# T15_PRI_SYS_V1_0.net
KiCad netlist of a schematic drawn in EAGLE
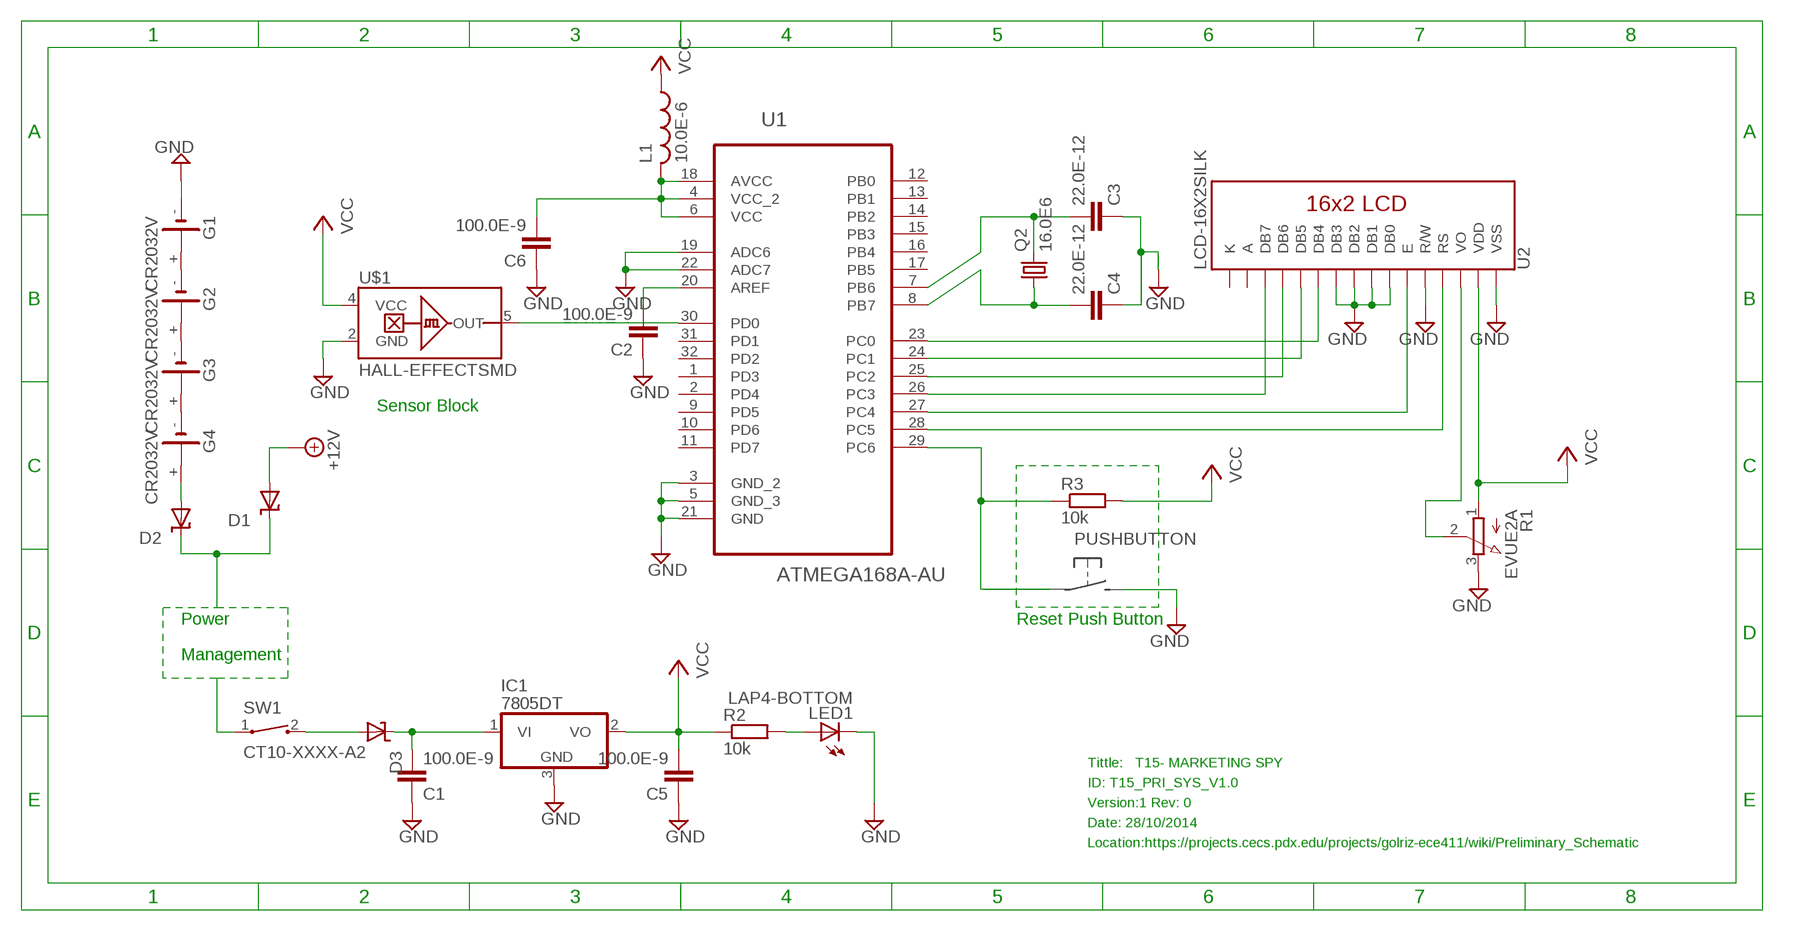
[diagram p0: schematic, sheet 1]

(export (version "E")
  (design (tool "Eeschema 10.0.6"))
  (components
    (comp (ref "C1")
      (value "100.0E-9")
      (footprint "eagle-import:C025-024X044")
      (libsource (lib "eagle-import") (part "C-EU025-024X044"))
    )
    (comp (ref "C2")
      (value "100.0E-9")
      (footprint "eagle-import:C025-024X044")
      (libsource (lib "eagle-import") (part "C-EU025-024X044"))
    )
    (comp (ref "C3")
      (value "22.0E-12")
      (footprint "eagle-import:C025-024X044")
      (libsource (lib "eagle-import") (part "C-EU025-024X044"))
    )
    (comp (ref "C4")
      (value "22.0E-12")
      (footprint "eagle-import:C025-024X044")
      (libsource (lib "eagle-import") (part "C-EU025-024X044"))
    )
    (comp (ref "C5")
      (value "100.0E-9")
      (footprint "eagle-import:C025-024X044")
      (libsource (lib "eagle-import") (part "C-EU025-024X044"))
    )
    (comp (ref "C6")
      (value "100.0E-9")
      (footprint "eagle-import:C025-024X044")
      (libsource (lib "eagle-import") (part "C-EU025-024X044"))
    )
    (comp (ref "D1")
      (value "SUPPRESSOR-SMBJ")
      (footprint "eagle-import:SMBJ")
      (libsource (lib "eagle-import") (part "SUPPRESSOR-SMBJ"))
    )
    (comp (ref "D2")
      (value "SUPPRESSOR-SMBJ")
      (footprint "eagle-import:SMBJ")
      (libsource (lib "eagle-import") (part "SUPPRESSOR-SMBJ"))
    )
    (comp (ref "D3")
      (value "SUPPRESSOR-SMBJ")
      (footprint "eagle-import:SMBJ")
      (libsource (lib "eagle-import") (part "SUPPRESSOR-SMBJ"))
    )
    (comp (ref "G1")
      (value "CR2032V")
      (footprint "eagle-import:CR2032V")
      (libsource (lib "eagle-import") (part "CR2032V"))
    )
    (comp (ref "G2")
      (value "CR2032V")
      (footprint "eagle-import:CR2032V")
      (libsource (lib "eagle-import") (part "CR2032V"))
    )
    (comp (ref "G3")
      (value "CR2032V")
      (footprint "eagle-import:CR2032V")
      (libsource (lib "eagle-import") (part "CR2032V"))
    )
    (comp (ref "G4")
      (value "CR2032V")
      (footprint "eagle-import:CR2032V")
      (libsource (lib "eagle-import") (part "CR2032V"))
    )
    (comp (ref "IC1")
      (value "7805DT")
      (footprint "eagle-import:TO252")
      (libsource (lib "eagle-import") (part "78DT05"))
    )
    (comp (ref "L1")
      (value "10.0E-6")
      (footprint "eagle-import:0204_5")
      (libsource (lib "eagle-import") (part "L-US0204/5"))
    )
    (comp (ref "LED1")
      (value "LAP4-BOTTOM")
      (footprint "eagle-import:P47F-BOTTOM")
      (libsource (lib "eagle-import") (part "P4-BOTTOMLA"))
    )
    (comp (ref "Q2")
      (value "16.0E6")
      (footprint "eagle-import:HC49_S")
      (libsource (lib "eagle-import") (part "CRYSTALHC49S"))
    )
    (comp (ref "R1")
      (value "EVUE2A")
      (footprint "eagle-import:EVUE")
      (libsource (lib "eagle-import") (part "EVUE2A"))
    )
    (comp (ref "R2")
      (value "10k")
      (footprint "eagle-import:0204_5")
      (libsource (lib "eagle-import") (part "R-EU_0204/5"))
    )
    (comp (ref "R3")
      (value "10k")
      (footprint "eagle-import:0204_5")
      (libsource (lib "eagle-import") (part "R-EU_0204/5"))
    )
    (comp (ref "SW1")
      (value "CT10-XXXX-A2")
      (footprint "eagle-import:CT10-XXXX-A2")
      (libsource (lib "eagle-import") (part "CT10-XXXX-A2"))
    )
    (comp (ref "U$1")
      (value "HALL-EFFECTSMD")
      (footprint "eagle-import:SC70")
      (libsource (lib "eagle-import") (part "HALL-EFFECTSMD"))
    )
    (comp (ref "U1")
      (value "ATMEGA168A-AU")
      (footprint "eagle-import:QFP80P900X900X120-32N")
      (libsource (lib "eagle-import") (part "ATMEGA168A-AU"))
    )
    (comp (ref "U2")
      (value "LCD-16X2SILK")
      (footprint "eagle-import:LCD-16X2")
      (libsource (lib "eagle-import") (part "LCD-16X2SILK"))
    )
  )
  (nets
    (net (code "1") (name "+12V") (class "Default")
      (node (ref "D1") (pin "A") (pinfunction "A_A") (pintype "passive"))
    )
    (net (code "2") (name "/A") (class "Default")
      (node (ref "U2") (pin "15") (pinfunction "A_15") (pintype "power_in"))
    )
    (net (code "3") (name "/K") (class "Default")
      (node (ref "U2") (pin "16") (pinfunction "K_16") (pintype "power_in"))
    )
    (net (code "4") (name "GND") (class "Default")
      (node (ref "C1") (pin "1") (pinfunction "1_1") (pintype "passive"))
      (node (ref "C2") (pin "1") (pinfunction "1_1") (pintype "passive"))
      (node (ref "C3") (pin "1") (pinfunction "1_1") (pintype "passive"))
      (node (ref "C4") (pin "1") (pinfunction "1_1") (pintype "passive"))
      (node (ref "C5") (pin "1") (pinfunction "1_1") (pintype "passive"))
      (node (ref "C6") (pin "1") (pinfunction "1_1") (pintype "passive"))
      (node (ref "G1") (pin "-") (pinfunction "-_-") (pintype "passive"))
      (node (ref "IC1") (pin "3") (pinfunction "GND_3") (pintype "passive"))
      (node (ref "LED1") (pin "C") (pinfunction "C_C") (pintype "passive"))
      (node (ref "R1") (pin "3") (pinfunction "E_3") (pintype "passive"))
      (node (ref "U$1") (pin "2") (pinfunction "GND_2") (pintype "bidirectional"))
      (node (ref "U1") (pin "19") (pinfunction "ADC6_19") (pintype "input"))
      (node (ref "U1") (pin "21") (pinfunction "GND_21") (pintype "passive"))
      (node (ref "U1") (pin "22") (pinfunction "ADC7_22") (pintype "input"))
      (node (ref "U1") (pin "3") (pinfunction "GND_2_3") (pintype "passive"))
      (node (ref "U1") (pin "5") (pinfunction "GND_3_5") (pintype "passive"))
      (node (ref "U2") (pin "1") (pinfunction "VSS_1") (pintype "power_in"))
      (node (ref "U2") (pin "10") (pinfunction "DB3_10") (pintype "bidirectional"))
      (node (ref "U2") (pin "5") (pinfunction "R/W_5") (pintype "input"))
      (node (ref "U2") (pin "7") (pinfunction "DB0_7") (pintype "bidirectional"))
      (node (ref "U2") (pin "8") (pinfunction "DB1_8") (pintype "bidirectional"))
      (node (ref "U2") (pin "9") (pinfunction "DB2_9") (pintype "bidirectional"))
    )
    (net (code "5") (name "Net-(D1-PadC)") (class "Default")
      (node (ref "D1") (pin "C") (pinfunction "C_C") (pintype "passive"))
      (node (ref "D2") (pin "C") (pinfunction "C_C") (pintype "passive"))
      (node (ref "SW1") (pin "1") (pinfunction "1_1") (pintype "passive"))
    )
    (net (code "6") (name "Net-(D2-PadA)") (class "Default")
      (node (ref "D2") (pin "A") (pinfunction "A_A") (pintype "passive"))
      (node (ref "G4") (pin "+") (pinfunction "+_+") (pintype "passive"))
    )
    (net (code "7") (name "Net-(D3-PadA)") (class "Default")
      (node (ref "D3") (pin "A") (pinfunction "A_A") (pintype "passive"))
      (node (ref "SW1") (pin "2") (pinfunction "2_2") (pintype "passive"))
    )
    (net (code "8") (name "Net-(G1-Pad+)") (class "Default")
      (node (ref "G1") (pin "+") (pinfunction "+_+") (pintype "passive"))
      (node (ref "G2") (pin "-") (pinfunction "-_-") (pintype "passive"))
    )
    (net (code "9") (name "Net-(G2-Pad+)") (class "Default")
      (node (ref "G2") (pin "+") (pinfunction "+_+") (pintype "passive"))
      (node (ref "G3") (pin "-") (pinfunction "-_-") (pintype "passive"))
    )
    (net (code "10") (name "Net-(G3-Pad+)") (class "Default")
      (node (ref "G3") (pin "+") (pinfunction "+_+") (pintype "passive"))
      (node (ref "G4") (pin "-") (pinfunction "-_-") (pintype "passive"))
    )
    (net (code "11") (name "Net-(IC1-VI)") (class "Default")
      (node (ref "C1") (pin "2") (pinfunction "2_2") (pintype "passive"))
      (node (ref "D3") (pin "C") (pinfunction "C_C") (pintype "passive"))
      (node (ref "IC1") (pin "1") (pinfunction "VI_1") (pintype "input"))
    )
    (net (code "12") (name "Net-(LED1-PadA)") (class "Default")
      (node (ref "LED1") (pin "A") (pinfunction "A_A") (pintype "passive"))
      (node (ref "R2") (pin "2") (pinfunction "2_2") (pintype "passive"))
    )
    (net (code "13") (name "Net-(R1-S)") (class "Default")
      (node (ref "R1") (pin "2") (pinfunction "S_2") (pintype "passive"))
      (node (ref "U2") (pin "3") (pinfunction "VO_3") (pintype "bidirectional"))
    )
    (net (code "14") (name "Net-(U$1-OUT)") (class "Default")
      (node (ref "U$1") (pin "5") (pinfunction "OUT_5") (pintype "bidirectional"))
      (node (ref "U1") (pin "30") (pinfunction "PD0_30") (pintype "bidirectional"))
    )
    (net (code "15") (name "Net-(U1-AREF)") (class "Default")
      (node (ref "C2") (pin "2") (pinfunction "2_2") (pintype "passive"))
      (node (ref "U1") (pin "20") (pinfunction "AREF_20") (pintype "input"))
    )
    (net (code "16") (name "Net-(U1-AVCC)") (class "Default")
      (node (ref "C6") (pin "2") (pinfunction "2_2") (pintype "passive"))
      (node (ref "L1") (pin "2") (pinfunction "2_2") (pintype "passive"))
      (node (ref "U1") (pin "18") (pinfunction "AVCC_18") (pintype "power_in"))
      (node (ref "U1") (pin "4") (pinfunction "VCC_2_4") (pintype "power_in"))
      (node (ref "U1") (pin "6") (pinfunction "VCC_6") (pintype "power_in"))
    )
    (net (code "17") (name "Net-(U1-PB6)") (class "Default")
      (node (ref "C3") (pin "2") (pinfunction "2_2") (pintype "passive"))
      (node (ref "Q2") (pin "2") (pinfunction "2_2") (pintype "passive"))
      (node (ref "U1") (pin "7") (pinfunction "PB6_7") (pintype "bidirectional"))
    )
    (net (code "18") (name "Net-(U1-PB7)") (class "Default")
      (node (ref "C4") (pin "2") (pinfunction "2_2") (pintype "passive"))
      (node (ref "Q2") (pin "1") (pinfunction "1_1") (pintype "passive"))
      (node (ref "U1") (pin "8") (pinfunction "PB7_8") (pintype "bidirectional"))
    )
    (net (code "19") (name "Net-(U1-PC0)") (class "Default")
      (node (ref "U1") (pin "23") (pinfunction "PC0_23") (pintype "bidirectional"))
      (node (ref "U2") (pin "11") (pinfunction "DB4_11") (pintype "bidirectional"))
    )
    (net (code "20") (name "Net-(U1-PC1)") (class "Default")
      (node (ref "U1") (pin "24") (pinfunction "PC1_24") (pintype "bidirectional"))
      (node (ref "U2") (pin "12") (pinfunction "DB5_12") (pintype "bidirectional"))
    )
    (net (code "21") (name "Net-(U1-PC2)") (class "Default")
      (node (ref "U1") (pin "25") (pinfunction "PC2_25") (pintype "bidirectional"))
      (node (ref "U2") (pin "13") (pinfunction "DB6_13") (pintype "bidirectional"))
    )
    (net (code "22") (name "Net-(U1-PC3)") (class "Default")
      (node (ref "U1") (pin "26") (pinfunction "PC3_26") (pintype "bidirectional"))
      (node (ref "U2") (pin "14") (pinfunction "DB7_14") (pintype "bidirectional"))
    )
    (net (code "23") (name "Net-(U1-PC4)") (class "Default")
      (node (ref "U1") (pin "27") (pinfunction "PC4_27") (pintype "bidirectional"))
      (node (ref "U2") (pin "6") (pinfunction "E_6") (pintype "input"))
    )
    (net (code "24") (name "Net-(U1-PC5)") (class "Default")
      (node (ref "U1") (pin "28") (pinfunction "PC5_28") (pintype "bidirectional"))
      (node (ref "U2") (pin "4") (pinfunction "RS_4") (pintype "input"))
    )
    (net (code "25") (name "Net-(U1-PC6)") (class "Default")
      (node (ref "R3") (pin "1") (pinfunction "1_1") (pintype "passive"))
      (node (ref "U1") (pin "29") (pinfunction "PC6_29") (pintype "bidirectional"))
    )
    (net (code "26") (name "VCC") (class "Default")
      (node (ref "C5") (pin "2") (pinfunction "2_2") (pintype "passive"))
      (node (ref "IC1") (pin "2") (pinfunction "VO_2") (pintype "passive"))
      (node (ref "L1") (pin "1") (pinfunction "1_1") (pintype "passive"))
      (node (ref "R1") (pin "1") (pinfunction "A_1") (pintype "passive"))
      (node (ref "R2") (pin "1") (pinfunction "1_1") (pintype "passive"))
      (node (ref "R3") (pin "2") (pinfunction "2_2") (pintype "passive"))
      (node (ref "U$1") (pin "4") (pinfunction "VCC_4") (pintype "bidirectional"))
      (node (ref "U2") (pin "2") (pinfunction "VDD_2") (pintype "power_in"))
    )
    (net (code "27") (name "unconnected-(G1-+-Pad+@1)") (class "Default")
      (node (ref "G1") (pin "+@1") (pinfunction "+_+@1") (pintype "passive"))
    )
    (net (code "28") (name "unconnected-(G2-+-Pad+@1)") (class "Default")
      (node (ref "G2") (pin "+@1") (pinfunction "+_+@1") (pintype "passive"))
    )
    (net (code "29") (name "unconnected-(G3-+-Pad+@1)") (class "Default")
      (node (ref "G3") (pin "+@1") (pinfunction "+_+@1") (pintype "passive"))
    )
    (net (code "30") (name "unconnected-(G4-+-Pad+@1)") (class "Default")
      (node (ref "G4") (pin "+@1") (pinfunction "+_+@1") (pintype "passive"))
    )
    (net (code "31") (name "unconnected-(U1-PB0-Pad12)") (class "Default")
      (node (ref "U1") (pin "12") (pinfunction "PB0_12") (pintype "bidirectional"))
    )
    (net (code "32") (name "unconnected-(U1-PB1-Pad13)") (class "Default")
      (node (ref "U1") (pin "13") (pinfunction "PB1_13") (pintype "bidirectional"))
    )
    (net (code "33") (name "unconnected-(U1-PB2-Pad14)") (class "Default")
      (node (ref "U1") (pin "14") (pinfunction "PB2_14") (pintype "bidirectional"))
    )
    (net (code "34") (name "unconnected-(U1-PB3-Pad15)") (class "Default")
      (node (ref "U1") (pin "15") (pinfunction "PB3_15") (pintype "bidirectional"))
    )
    (net (code "35") (name "unconnected-(U1-PB4-Pad16)") (class "Default")
      (node (ref "U1") (pin "16") (pinfunction "PB4_16") (pintype "bidirectional"))
    )
    (net (code "36") (name "unconnected-(U1-PB5-Pad17)") (class "Default")
      (node (ref "U1") (pin "17") (pinfunction "PB5_17") (pintype "bidirectional"))
    )
    (net (code "37") (name "unconnected-(U1-PD1-Pad31)") (class "Default")
      (node (ref "U1") (pin "31") (pinfunction "PD1_31") (pintype "bidirectional"))
    )
    (net (code "38") (name "unconnected-(U1-PD2-Pad32)") (class "Default")
      (node (ref "U1") (pin "32") (pinfunction "PD2_32") (pintype "bidirectional"))
    )
    (net (code "39") (name "unconnected-(U1-PD3-Pad1)") (class "Default")
      (node (ref "U1") (pin "1") (pinfunction "PD3_1") (pintype "bidirectional"))
    )
    (net (code "40") (name "unconnected-(U1-PD4-Pad2)") (class "Default")
      (node (ref "U1") (pin "2") (pinfunction "PD4_2") (pintype "bidirectional"))
    )
    (net (code "41") (name "unconnected-(U1-PD5-Pad9)") (class "Default")
      (node (ref "U1") (pin "9") (pinfunction "PD5_9") (pintype "bidirectional"))
    )
    (net (code "42") (name "unconnected-(U1-PD6-Pad10)") (class "Default")
      (node (ref "U1") (pin "10") (pinfunction "PD6_10") (pintype "bidirectional"))
    )
    (net (code "43") (name "unconnected-(U1-PD7-Pad11)") (class "Default")
      (node (ref "U1") (pin "11") (pinfunction "PD7_11") (pintype "bidirectional"))
    )
  )
)
